# Sheet_dht11.net
KiCad netlist of a schematic drawn in Altium Designer
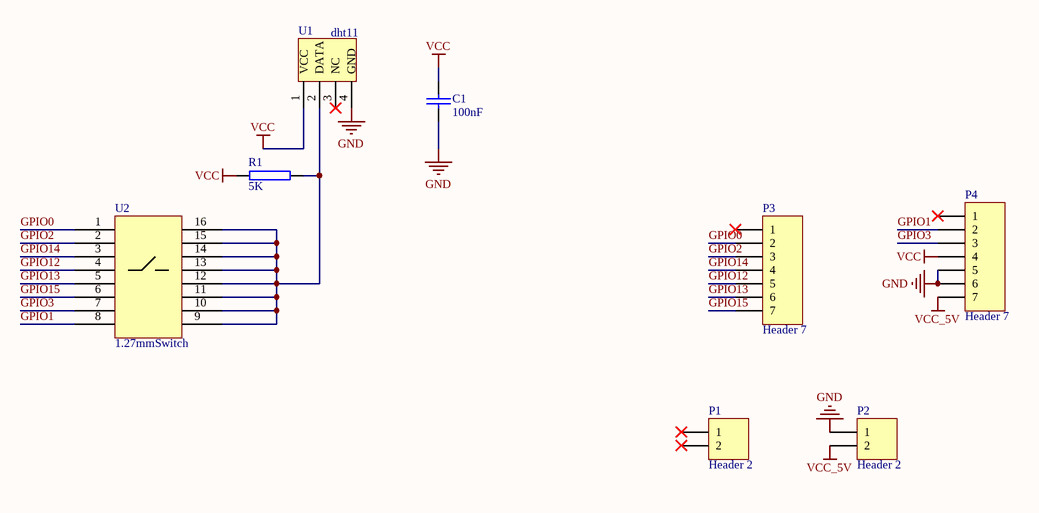
[diagram p0: Sheet_dht11.SchDoc]

(export (version "E")
  (design (tool "Eeschema 10.0.6"))
  (components
    (comp (ref "C1")
      (value "100nF")
      (footprint "C0603")
      (description "贴片电容")
      (libsource (lib "Schlib_OLEDMCU") (part "C0603"))
    )
    (comp (ref "P1")
      (value "Header 2")
      (footprint "HDR1X2")
      (description "Header, 2-Pin")
      (fields (field (name "PUBLISHER") "Altium Limited"))
      (libsource (lib "Miscellaneous Connectors") (part "Header 2"))
    )
    (comp (ref "P2")
      (value "Header 2")
      (footprint "HDR1X2")
      (description "Header, 2-Pin")
      (fields (field (name "PUBLISHER") "Altium Limited"))
      (libsource (lib "Miscellaneous Connectors") (part "Header 2"))
    )
    (comp (ref "P3")
      (value "Header 7")
      (footprint "HDR1X7")
      (description "Header, 7-Pin")
      (fields (field (name "PUBLISHER") "Altium Limited"))
      (libsource (lib "Miscellaneous Connectors") (part "Header 7"))
    )
    (comp (ref "P4")
      (value "Header 7")
      (footprint "HDR1X7")
      (description "Header, 7-Pin")
      (fields (field (name "PUBLISHER") "Altium Limited"))
      (libsource (lib "Miscellaneous Connectors") (part "Header 7"))
    )
    (comp (ref "R1")
      (value "5K")
      (footprint "R0603")
      (description "贴片电阻")
      (libsource (lib "Schlib_OLEDMCU") (part "R0603"))
    )
    (comp (ref "U1")
      (value "dht11")
      (footprint "dht11")
      (description "温湿度传感器")
      (libsource (lib "Schlib_OLEDMCU") (part "dht11"))
    )
    (comp (ref "U2")
      (value "1.27mmSwitch")
      (footprint "NumberSwitch")
      (description "拨码开关")
      (libsource (lib "Schlib_OLEDMCU") (part "NumberSwitch"))
    )
  )
  (nets
    (net (code "1") (name "/GPIO0") (class "Default")
      (node (ref "P3") (pin "2") (pinfunction "2_2") (pintype "passive"))
      (node (ref "U2") (pin "1") (pinfunction "1_1") (pintype "passive"))
    )
    (net (code "2") (name "/GPIO1") (class "Default")
      (node (ref "P4") (pin "2") (pinfunction "2_2") (pintype "passive"))
      (node (ref "U2") (pin "8") (pinfunction "8_8") (pintype "passive"))
    )
    (net (code "3") (name "/GPIO2") (class "Default")
      (node (ref "P3") (pin "3") (pinfunction "3_3") (pintype "passive"))
      (node (ref "U2") (pin "2") (pinfunction "2_2") (pintype "passive"))
    )
    (net (code "4") (name "/GPIO3") (class "Default")
      (node (ref "P4") (pin "3") (pinfunction "3_3") (pintype "passive"))
      (node (ref "U2") (pin "7") (pinfunction "7_7") (pintype "passive"))
    )
    (net (code "5") (name "/GPIO12") (class "Default")
      (node (ref "P3") (pin "5") (pinfunction "5_5") (pintype "passive"))
      (node (ref "U2") (pin "4") (pinfunction "4_4") (pintype "passive"))
    )
    (net (code "6") (name "/GPIO13") (class "Default")
      (node (ref "P3") (pin "6") (pinfunction "6_6") (pintype "passive"))
      (node (ref "U2") (pin "5") (pinfunction "5_5") (pintype "passive"))
    )
    (net (code "7") (name "/GPIO14") (class "Default")
      (node (ref "P3") (pin "4") (pinfunction "4_4") (pintype "passive"))
      (node (ref "U2") (pin "3") (pinfunction "3_3") (pintype "passive"))
    )
    (net (code "8") (name "/GPIO15") (class "Default")
      (node (ref "P3") (pin "7") (pinfunction "7_7") (pintype "passive"))
      (node (ref "U2") (pin "6") (pinfunction "6_6") (pintype "passive"))
    )
    (net (code "9") (name "GND") (class "Default")
      (node (ref "C1") (pin "2") (pinfunction "2_2") (pintype "passive"))
      (node (ref "P2") (pin "1") (pinfunction "1_1") (pintype "passive"))
      (node (ref "P4") (pin "5") (pinfunction "5_5") (pintype "passive"))
      (node (ref "P4") (pin "6") (pinfunction "6_6") (pintype "passive"))
      (node (ref "U1") (pin "4") (pinfunction "GND_4") (pintype "passive"))
    )
    (net (code "10") (name "Net-(U1-DATA)") (class "Default")
      (node (ref "R1") (pin "2") (pinfunction "2_2") (pintype "passive"))
      (node (ref "U1") (pin "2") (pinfunction "DATA_2") (pintype "passive"))
      (node (ref "U2") (pin "10") (pinfunction "10_10") (pintype "passive"))
      (node (ref "U2") (pin "11") (pinfunction "11_11") (pintype "passive"))
      (node (ref "U2") (pin "12") (pinfunction "12_12") (pintype "passive"))
      (node (ref "U2") (pin "13") (pinfunction "13_13") (pintype "passive"))
      (node (ref "U2") (pin "14") (pinfunction "14_14") (pintype "passive"))
      (node (ref "U2") (pin "15") (pinfunction "15_15") (pintype "passive"))
      (node (ref "U2") (pin "16") (pinfunction "16_16") (pintype "passive"))
      (node (ref "U2") (pin "9") (pinfunction "9_9") (pintype "passive"))
    )
    (net (code "11") (name "VCC") (class "Default")
      (node (ref "C1") (pin "1") (pinfunction "1_1") (pintype "passive"))
      (node (ref "P4") (pin "4") (pinfunction "4_4") (pintype "passive"))
      (node (ref "R1") (pin "1") (pinfunction "1_1") (pintype "passive"))
      (node (ref "U1") (pin "1") (pinfunction "VCC_1") (pintype "passive"))
    )
    (net (code "12") (name "VCC_5V") (class "Default")
      (node (ref "P2") (pin "2") (pinfunction "2_2") (pintype "passive"))
      (node (ref "P4") (pin "7") (pinfunction "7_7") (pintype "passive"))
    )
    (net (code "13") (name "unconnected-(P1-Pad1)") (class "Default")
      (node (ref "P1") (pin "1") (pinfunction "1_1") (pintype "passive+no_connect"))
    )
    (net (code "14") (name "unconnected-(P1-Pad2)") (class "Default")
      (node (ref "P1") (pin "2") (pinfunction "2_2") (pintype "passive+no_connect"))
    )
    (net (code "15") (name "unconnected-(P3-Pad1)") (class "Default")
      (node (ref "P3") (pin "1") (pinfunction "1_1") (pintype "passive+no_connect"))
    )
    (net (code "16") (name "unconnected-(P4-Pad1)") (class "Default")
      (node (ref "P4") (pin "1") (pinfunction "1_1") (pintype "passive+no_connect"))
    )
    (net (code "17") (name "unconnected-(U1-NC-Pad3)") (class "Default")
      (node (ref "U1") (pin "3") (pinfunction "NC_3") (pintype "passive+no_connect"))
    )
  )
)
